# PressureSensorCircuit.net
KiCad netlist of a schematic drawn in Altium Designer
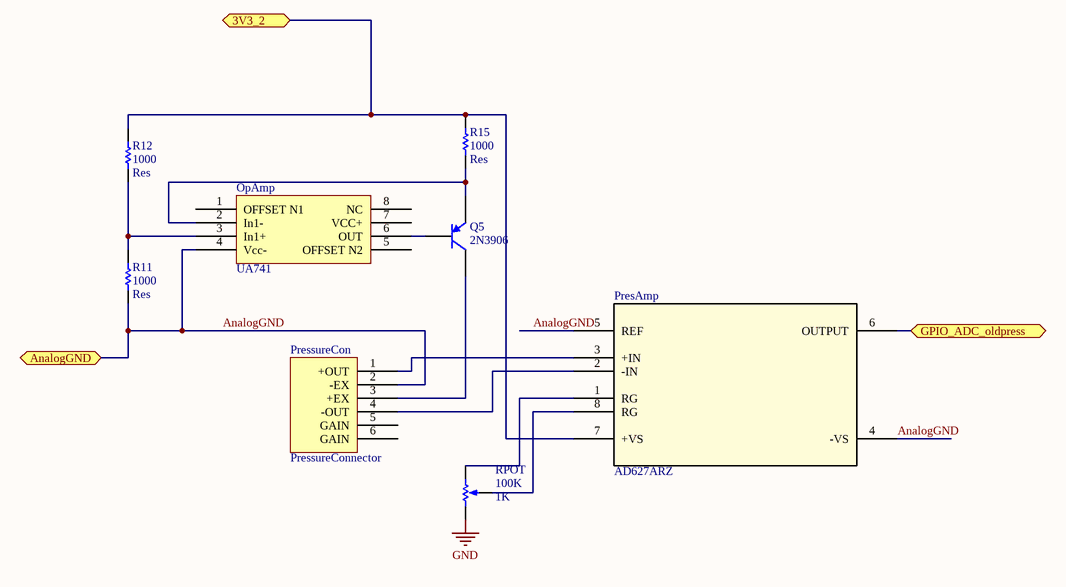
[diagram p0: PressureSensorCircuit.SchDoc]

(export (version "E")
  (design (tool "Eeschema 10.0.6"))
  (components
    (comp (ref "OpAmp")
      (value "UA741")
      (footprint "UmbilicalConnectors:UA741")
      (libsource (lib "UmbilicalBoardV2") (part "UA741"))
    )
    (comp (ref "PresAmp")
      (value "AD627ARZ")
      (footprint "R_8")
      (description "Imported")
      (libsource (lib "2016-04-06_02-20-10") (part "AD627ARZ"))
    )
    (comp (ref "PressureCon")
      (value "PressureConnector")
      (footprint "UmbilicalConnectors:Pressure Connector")
      (description "Molex 53261-0671")
      (libsource (lib "UmbilicalBoardV2") (part "PressureConnector"))
    )
    (comp (ref "Q5")
      (value "2N3906")
      (footprint "TO-92A")
      (description "PNP General Purpose Amplifier")
      (fields (field (name "PUBLISHER") "Altium Limited"))
      (libsource (lib "Miscellaneous Devices") (part "2N3906"))
    )
    (comp (ref "R11")
      (value "1000")
      (footprint "AXIAL-0.3")
      (description "Resistor- 696-1552-ND")
      (fields (field (name "ALTIUM_VALUE") "Res") (field (name "PUBLISHER") "Altium Limited"))
      (libsource (lib "Miscellaneous Devices") (part "Res1"))
    )
    (comp (ref "R12")
      (value "1000")
      (footprint "AXIAL-0.3")
      (description "Resistor- 696-1552-ND")
      (fields (field (name "ALTIUM_VALUE") "Res") (field (name "PUBLISHER") "Altium Limited"))
      (libsource (lib "Miscellaneous Devices") (part "Res1"))
    )
    (comp (ref "R15")
      (value "1000")
      (footprint "AXIAL-0.3")
      (description "Resistor- 696-1552-ND")
      (fields (field (name "ALTIUM_VALUE") "Res") (field (name "PUBLISHER") "Altium Limited"))
      (libsource (lib "Miscellaneous Devices") (part "Res1"))
    )
    (comp (ref "RPOT")
      (value "100K")
      (footprint "VR5")
      (description "Potentiometer")
      (fields (field (name "ALTIUM_VALUE") "1K") (field (name "PUBLISHER") "Altium Limited"))
      (libsource (lib "Miscellaneous Devices") (part "RPot"))
    )
  )
  (nets
    (net (code "1") (name "/3V3_2") (class "Default")
      (node (ref "PresAmp") (pin "7") (pinfunction "+VS_7") (pintype "passive"))
      (node (ref "R12") (pin "1") (pinfunction "1_1") (pintype "passive"))
      (node (ref "R15") (pin "1") (pinfunction "1_1") (pintype "passive"))
    )
    (net (code "2") (name "/AnalogGND") (class "Default")
      (node (ref "OpAmp") (pin "4") (pinfunction "Vcc-_4") (pintype "passive"))
      (node (ref "PresAmp") (pin "4") (pinfunction "-VS_4") (pintype "passive"))
      (node (ref "PresAmp") (pin "5") (pinfunction "REF_5") (pintype "passive"))
      (node (ref "PressureCon") (pin "2") (pinfunction "-EX_2") (pintype "passive"))
      (node (ref "R11") (pin "2") (pinfunction "2_2") (pintype "passive"))
    )
    (net (code "3") (name "/GPIO_ADC_oldpress") (class "Default")
      (node (ref "PresAmp") (pin "6") (pinfunction "OUTPUT_6") (pintype "passive"))
    )
    (net (code "4") (name "GND") (class "Default")
      (node (ref "RPOT") (pin "1") (pinfunction "TOP_1") (pintype "passive"))
    )
    (net (code "5") (name "Net-(OpAmp-In1+)") (class "Default")
      (node (ref "OpAmp") (pin "3") (pinfunction "In1+_3") (pintype "passive"))
      (node (ref "R11") (pin "1") (pinfunction "1_1") (pintype "passive"))
      (node (ref "R12") (pin "2") (pinfunction "2_2") (pintype "passive"))
    )
    (net (code "6") (name "Net-(OpAmp-In1-)") (class "Default")
      (node (ref "OpAmp") (pin "2") (pinfunction "In1-_2") (pintype "passive"))
      (node (ref "Q5") (pin "1") (pinfunction "E_1") (pintype "passive"))
      (node (ref "R15") (pin "2") (pinfunction "2_2") (pintype "passive"))
    )
    (net (code "7") (name "Net-(OpAmp-OUT)") (class "Default")
      (node (ref "OpAmp") (pin "6") (pinfunction "OUT_6") (pintype "passive"))
      (node (ref "Q5") (pin "2") (pinfunction "B_2") (pintype "passive"))
    )
    (net (code "8") (name "Net-(PresAmp-+IN)") (class "Default")
      (node (ref "PresAmp") (pin "3") (pinfunction "+IN_3") (pintype "passive"))
      (node (ref "PressureCon") (pin "1") (pinfunction "+OUT_1") (pintype "passive"))
    )
    (net (code "9") (name "Net-(PresAmp--IN)") (class "Default")
      (node (ref "PresAmp") (pin "2") (pinfunction "-IN_2") (pintype "passive"))
      (node (ref "PressureCon") (pin "4") (pinfunction "-OUT_4") (pintype "passive"))
    )
    (net (code "10") (name "Net-(PressureCon-+EX)") (class "Default")
      (node (ref "PressureCon") (pin "3") (pinfunction "+EX_3") (pintype "passive"))
      (node (ref "Q5") (pin "3") (pinfunction "C_3") (pintype "passive"))
    )
    (net (code "11") (name "Net-(RPOT-BOT)") (class "Default")
      (node (ref "PresAmp") (pin "1") (pinfunction "RG_1") (pintype "passive"))
      (node (ref "RPOT") (pin "2") (pinfunction "BOT_2") (pintype "passive"))
    )
    (net (code "12") (name "Net-(RPOT-TAP)") (class "Default")
      (node (ref "PresAmp") (pin "8") (pinfunction "RG_8") (pintype "passive"))
      (node (ref "RPOT") (pin "3") (pinfunction "TAP_3") (pintype "passive"))
    )
    (net (code "13") (name "unconnected-(OpAmp-NC-Pad8)") (class "Default")
      (node (ref "OpAmp") (pin "8") (pinfunction "NC_8") (pintype "passive"))
    )
    (net (code "14") (name "unconnected-(OpAmp-OFFSET_N1-Pad1)") (class "Default")
      (node (ref "OpAmp") (pin "1") (pinfunction "OFFSET_N1_1") (pintype "passive"))
    )
    (net (code "15") (name "unconnected-(OpAmp-OFFSET_N2-Pad5)") (class "Default")
      (node (ref "OpAmp") (pin "5") (pinfunction "OFFSET_N2_5") (pintype "passive"))
    )
    (net (code "16") (name "unconnected-(OpAmp-VCC+-Pad7)") (class "Default")
      (node (ref "OpAmp") (pin "7") (pinfunction "VCC+_7") (pintype "passive"))
    )
    (net (code "17") (name "unconnected-(PressureCon-GAIN-Pad5)") (class "Default")
      (node (ref "PressureCon") (pin "5") (pinfunction "GAIN_5") (pintype "passive"))
    )
    (net (code "18") (name "unconnected-(PressureCon-GAIN-Pad6)") (class "Default")
      (node (ref "PressureCon") (pin "6") (pinfunction "GAIN_6") (pintype "passive"))
    )
  )
)
